# Peripherals.net
KiCad netlist of a schematic drawn in Altium Designer
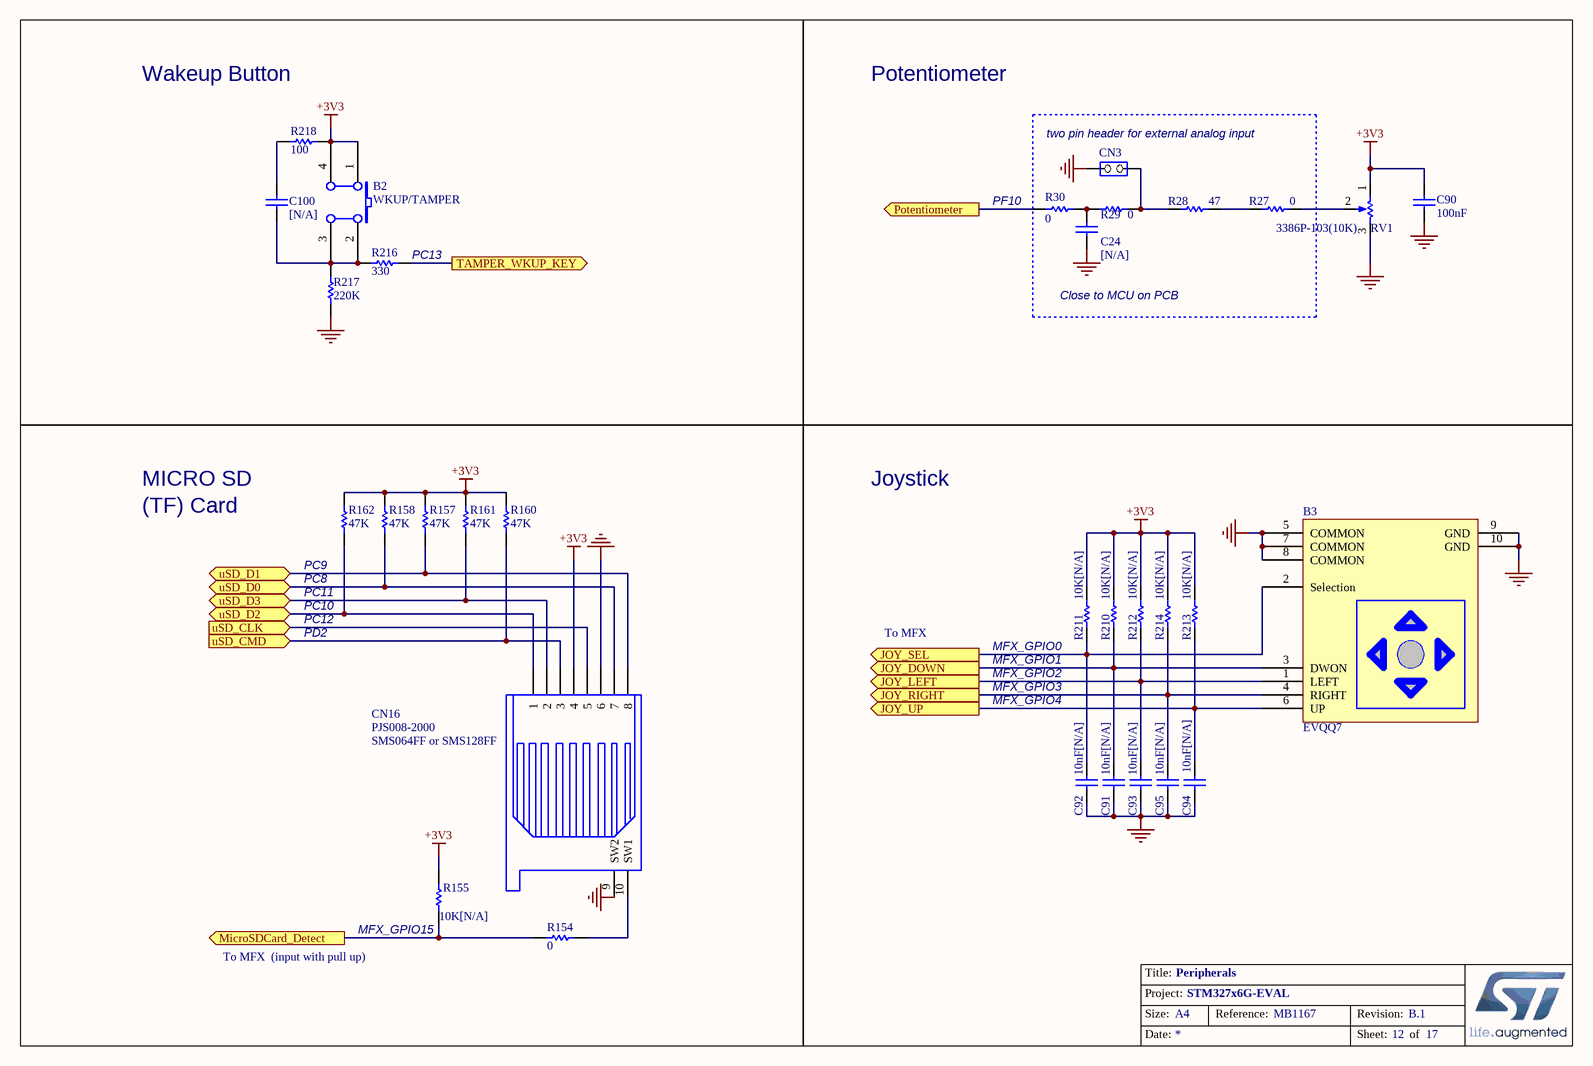
[diagram p0: Peripherals.SchDoc]

(export (version "E")
  (design (tool "Eeschema 10.0.6"))
  (components
    (comp (ref "B2")
      (value "WKUP/TAMPER")
      (footprint "PB10")
      (description "SE PUSHBUTTON")
      (libsource (lib "Documents") (part "SW PUSHBUTTON"))
    )
    (comp (ref "B3") (value "EVQQ7") (footprint "SW-JOY") (libsource (lib "mb1045") (part "EVQQ7")))
    (comp (ref "C24")
      (value "[N/A]")
      (footprint "0603C")
      (description "Capacitor")
      (fields (field (name "PUBLISHER") "Altium Limited"))
      (libsource (lib "Miscellaneous Devices") (part "cap"))
    )
    (comp (ref "C90")
      (value "100nF")
      (footprint "0603C")
      (description "Capacitor")
      (fields (field (name "PUBLISHER") "Altium Limited"))
      (libsource (lib "Miscellaneous Devices") (part "CAP"))
    )
    (comp (ref "C91")
      (value "10nF[N/A]")
      (footprint "0603C")
      (description "Capacitor")
      (fields (field (name "PUBLISHER") "Altium Limited"))
      (libsource (lib "Miscellaneous Devices") (part "CAP"))
    )
    (comp (ref "C92")
      (value "10nF[N/A]")
      (footprint "0603C")
      (description "Capacitor")
      (fields (field (name "PUBLISHER") "Altium Limited"))
      (libsource (lib "Miscellaneous Devices") (part "CAP"))
    )
    (comp (ref "C93")
      (value "10nF[N/A]")
      (footprint "0603C")
      (description "Capacitor")
      (fields (field (name "PUBLISHER") "Altium Limited"))
      (libsource (lib "Miscellaneous Devices") (part "CAP"))
    )
    (comp (ref "C94")
      (value "10nF[N/A]")
      (footprint "0603C")
      (description "Capacitor")
      (fields (field (name "PUBLISHER") "Altium Limited"))
      (libsource (lib "Miscellaneous Devices") (part "CAP"))
    )
    (comp (ref "C95")
      (value "10nF[N/A]")
      (footprint "0603C")
      (description "Capacitor")
      (fields (field (name "PUBLISHER") "Altium Limited"))
      (libsource (lib "Miscellaneous Devices") (part "CAP"))
    )
    (comp (ref "C100")
      (value "[N/A]")
      (footprint "0603C")
      (description "Capacitor")
      (fields (field (name "PUBLISHER") "Altium Limited"))
      (libsource (lib "Miscellaneous Devices") (part "CAP"))
    )
    (comp (ref "CN3") (value "~") (footprint "SIP2") (libsource (lib "*") (part "JP2")))
    (comp (ref "CN16")
      (value "PJS008-2000")
      (footprint "MSD_PJS008_")
      (libsource (lib "MB525") (part "SMS016AFA5E"))
    )
    (comp (ref "R27")
      (value "0")
      (footprint "0603R")
      (description "Resistor")
      (fields (field (name "PUBLISHER") "Altium Limited"))
      (libsource (lib "Miscellaneous Devices") (part "Res1"))
    )
    (comp (ref "R28")
      (value "47")
      (footprint "0603R")
      (description "Resistor")
      (fields (field (name "PUBLISHER") "Altium Limited"))
      (libsource (lib "Miscellaneous Devices") (part "Res1"))
    )
    (comp (ref "R29")
      (value "0")
      (footprint "0603R")
      (description "Resistor")
      (fields (field (name "PUBLISHER") "Altium Limited"))
      (libsource (lib "Miscellaneous Devices") (part "Res1"))
    )
    (comp (ref "R30")
      (value "0")
      (footprint "0603R")
      (description "Resistor")
      (fields (field (name "PUBLISHER") "Altium Limited"))
      (libsource (lib "Miscellaneous Devices") (part "Res1"))
    )
    (comp (ref "R154")
      (value "0")
      (footprint "0603R")
      (description "Resistor")
      (fields (field (name "PUBLISHER") "Altium Limited"))
      (libsource (lib "Miscellaneous Devices") (part "Res1"))
    )
    (comp (ref "R155")
      (value "10K[N/A]")
      (footprint "0603R")
      (description "Resistor")
      (fields (field (name "PUBLISHER") "Altium Limited"))
      (libsource (lib "Miscellaneous Devices") (part "Res1"))
    )
    (comp (ref "R157")
      (value "47K")
      (footprint "0603R")
      (description "Resistor")
      (fields (field (name "PUBLISHER") "Altium Limited"))
      (libsource (lib "Miscellaneous Devices") (part "res1"))
    )
    (comp (ref "R158")
      (value "47K")
      (footprint "0603R")
      (description "Resistor")
      (fields (field (name "PUBLISHER") "Altium Limited"))
      (libsource (lib "Miscellaneous Devices") (part "res1"))
    )
    (comp (ref "R160")
      (value "47K")
      (footprint "0603R")
      (description "Resistor")
      (fields (field (name "PUBLISHER") "Altium Limited"))
      (libsource (lib "Miscellaneous Devices") (part "res1"))
    )
    (comp (ref "R161")
      (value "47K")
      (footprint "0603R")
      (description "Resistor")
      (fields (field (name "PUBLISHER") "Altium Limited"))
      (libsource (lib "Miscellaneous Devices") (part "res1"))
    )
    (comp (ref "R162")
      (value "47K")
      (footprint "0603R")
      (description "Resistor")
      (fields (field (name "PUBLISHER") "Altium Limited"))
      (libsource (lib "Miscellaneous Devices") (part "res1"))
    )
    (comp (ref "R210")
      (value "10K[N/A]")
      (footprint "0603R")
      (description "Resistor")
      (fields (field (name "PUBLISHER") "Altium Limited"))
      (libsource (lib "Miscellaneous Devices") (part "res1"))
    )
    (comp (ref "R211")
      (value "10K[N/A]")
      (footprint "0603R")
      (description "Resistor")
      (fields (field (name "PUBLISHER") "Altium Limited"))
      (libsource (lib "Miscellaneous Devices") (part "res1"))
    )
    (comp (ref "R212")
      (value "10K[N/A]")
      (footprint "0603R")
      (description "Resistor")
      (fields (field (name "PUBLISHER") "Altium Limited"))
      (libsource (lib "Miscellaneous Devices") (part "res1"))
    )
    (comp (ref "R213")
      (value "10K[N/A]")
      (footprint "0603R")
      (description "Resistor")
      (fields (field (name "PUBLISHER") "Altium Limited"))
      (libsource (lib "Miscellaneous Devices") (part "res1"))
    )
    (comp (ref "R214")
      (value "10K[N/A]")
      (footprint "0603R")
      (description "Resistor")
      (fields (field (name "PUBLISHER") "Altium Limited"))
      (libsource (lib "Miscellaneous Devices") (part "res1"))
    )
    (comp (ref "R216")
      (value "330")
      (footprint "0603R")
      (description "Resistor")
      (fields (field (name "PUBLISHER") "Altium Limited"))
      (libsource (lib "Miscellaneous Devices") (part "Res1"))
    )
    (comp (ref "R217")
      (value "220K")
      (footprint "0603R")
      (description "Resistor")
      (fields (field (name "PUBLISHER") "Altium Limited"))
      (libsource (lib "Miscellaneous Devices") (part "res1"))
    )
    (comp (ref "R218")
      (value "100")
      (footprint "0603R")
      (description "Resistor")
      (fields (field (name "PUBLISHER") "Altium Limited"))
      (libsource (lib "Miscellaneous Devices") (part "Res1"))
    )
    (comp (ref "RV1")
      (value "3386P-103(10K)")
      (footprint "3386P")
      (libsource (lib "STR910_SCHLIB") (part "RV"))
    )
  )
  (nets
    (net (code "1") (name "+3V3") (class "Default")
      (node (ref "B2") (pin "1") (pinfunction "A0_1") (pintype "passive"))
      (node (ref "B2") (pin "4") (pinfunction "A1_4") (pintype "passive"))
      (node (ref "C90") (pin "1") (pinfunction "1_1") (pintype "passive"))
      (node (ref "CN16") (pin "4") (pinfunction "4_4") (pintype "passive"))
      (node (ref "R155") (pin "2") (pinfunction "2_2") (pintype "passive"))
      (node (ref "R157") (pin "1") (pinfunction "1_1") (pintype "passive"))
      (node (ref "R158") (pin "1") (pinfunction "1_1") (pintype "passive"))
      (node (ref "R160") (pin "1") (pinfunction "1_1") (pintype "passive"))
      (node (ref "R161") (pin "1") (pinfunction "1_1") (pintype "passive"))
      (node (ref "R162") (pin "1") (pinfunction "1_1") (pintype "passive"))
      (node (ref "R210") (pin "1") (pinfunction "1_1") (pintype "passive"))
      (node (ref "R211") (pin "1") (pinfunction "1_1") (pintype "passive"))
      (node (ref "R212") (pin "1") (pinfunction "1_1") (pintype "passive"))
      (node (ref "R213") (pin "1") (pinfunction "1_1") (pintype "passive"))
      (node (ref "R214") (pin "1") (pinfunction "1_1") (pintype "passive"))
      (node (ref "R218") (pin "1") (pinfunction "1_1") (pintype "passive"))
      (node (ref "RV1") (pin "1") (pinfunction "BOT_1") (pintype "passive"))
    )
    (net (code "2") (name "/JOY_DOWN") (class "Default")
      (node (ref "B3") (pin "3") (pinfunction "DWON_3") (pintype "passive"))
      (node (ref "C91") (pin "2") (pinfunction "2_2") (pintype "passive"))
      (node (ref "R210") (pin "2") (pinfunction "2_2") (pintype "passive"))
    )
    (net (code "3") (name "/JOY_LEFT") (class "Default")
      (node (ref "B3") (pin "1") (pinfunction "LEFT_1") (pintype "passive"))
      (node (ref "C93") (pin "2") (pinfunction "2_2") (pintype "passive"))
      (node (ref "R212") (pin "2") (pinfunction "2_2") (pintype "passive"))
    )
    (net (code "4") (name "/JOY_RIGHT") (class "Default")
      (node (ref "B3") (pin "4") (pinfunction "RIGHT_4") (pintype "passive"))
      (node (ref "C95") (pin "2") (pinfunction "2_2") (pintype "passive"))
      (node (ref "R214") (pin "2") (pinfunction "2_2") (pintype "passive"))
    )
    (net (code "5") (name "/JOY_SEL") (class "Default")
      (node (ref "B3") (pin "2") (pinfunction "Selection_2") (pintype "passive"))
      (node (ref "C92") (pin "2") (pinfunction "2_2") (pintype "passive"))
      (node (ref "R211") (pin "2") (pinfunction "2_2") (pintype "passive"))
    )
    (net (code "6") (name "/JOY_UP") (class "Default")
      (node (ref "B3") (pin "6") (pinfunction "UP_6") (pintype "passive"))
      (node (ref "C94") (pin "2") (pinfunction "2_2") (pintype "passive"))
      (node (ref "R213") (pin "2") (pinfunction "2_2") (pintype "passive"))
    )
    (net (code "7") (name "/MicroSDCard_Detect") (class "Default")
      (node (ref "R154") (pin "1") (pinfunction "1_1") (pintype "passive"))
      (node (ref "R155") (pin "1") (pinfunction "1_1") (pintype "passive"))
    )
    (net (code "8") (name "/Potentiometer") (class "Default")
      (node (ref "R30") (pin "2") (pinfunction "2_2") (pintype "passive"))
    )
    (net (code "9") (name "/TAMPER_WKUP_KEY") (class "Default")
      (node (ref "R216") (pin "2") (pinfunction "2_2") (pintype "passive"))
    )
    (net (code "10") (name "/uSD_CLK") (class "Default")
      (node (ref "CN16") (pin "5") (pinfunction "5_5") (pintype "passive"))
    )
    (net (code "11") (name "/uSD_CMD") (class "Default")
      (node (ref "CN16") (pin "3") (pinfunction "3_3") (pintype "passive"))
      (node (ref "R160") (pin "2") (pinfunction "2_2") (pintype "passive"))
    )
    (net (code "12") (name "/uSD_D0") (class "Default")
      (node (ref "CN16") (pin "7") (pinfunction "7_7") (pintype "passive"))
      (node (ref "R158") (pin "2") (pinfunction "2_2") (pintype "passive"))
    )
    (net (code "13") (name "/uSD_D1") (class "Default")
      (node (ref "CN16") (pin "8") (pinfunction "8_8") (pintype "passive"))
      (node (ref "R157") (pin "2") (pinfunction "2_2") (pintype "passive"))
    )
    (net (code "14") (name "/uSD_D2") (class "Default")
      (node (ref "CN16") (pin "1") (pinfunction "1_1") (pintype "passive"))
      (node (ref "R162") (pin "2") (pinfunction "2_2") (pintype "passive"))
    )
    (net (code "15") (name "/uSD_D3") (class "Default")
      (node (ref "CN16") (pin "2") (pinfunction "2_2") (pintype "passive"))
      (node (ref "R161") (pin "2") (pinfunction "2_2") (pintype "passive"))
    )
    (net (code "16") (name "GND") (class "Default")
      (node (ref "B3") (pin "10") (pinfunction "GND_10") (pintype "passive"))
      (node (ref "B3") (pin "5") (pinfunction "COMMON_5") (pintype "passive"))
      (node (ref "B3") (pin "7") (pinfunction "COMMON_7") (pintype "passive"))
      (node (ref "B3") (pin "8") (pinfunction "COMMON_8") (pintype "passive"))
      (node (ref "B3") (pin "9") (pinfunction "GND_9") (pintype "passive"))
      (node (ref "C24") (pin "1") (pinfunction "1_1") (pintype "passive"))
      (node (ref "C90") (pin "2") (pinfunction "2_2") (pintype "passive"))
      (node (ref "C91") (pin "1") (pinfunction "1_1") (pintype "passive"))
      (node (ref "C92") (pin "1") (pinfunction "1_1") (pintype "passive"))
      (node (ref "C93") (pin "1") (pinfunction "1_1") (pintype "passive"))
      (node (ref "C94") (pin "1") (pinfunction "1_1") (pintype "passive"))
      (node (ref "C95") (pin "1") (pinfunction "1_1") (pintype "passive"))
      (node (ref "CN16") (pin "6") (pinfunction "6_6") (pintype "passive"))
      (node (ref "CN16") (pin "9") (pinfunction "SW2_9") (pintype "passive"))
      (node (ref "CN3") (pin "2") (pinfunction "NO_2") (pintype "passive"))
      (node (ref "R217") (pin "2") (pinfunction "2_2") (pintype "passive"))
      (node (ref "RV1") (pin "3") (pinfunction "TOP_3") (pintype "passive"))
    )
    (net (code "17") (name "Net-(B2-B0)") (class "Default")
      (node (ref "B2") (pin "2") (pinfunction "B0_2") (pintype "passive"))
      (node (ref "B2") (pin "3") (pinfunction "B1_3") (pintype "passive"))
      (node (ref "C100") (pin "2") (pinfunction "2_2") (pintype "passive"))
      (node (ref "R216") (pin "1") (pinfunction "1_1") (pintype "passive"))
      (node (ref "R217") (pin "1") (pinfunction "1_1") (pintype "passive"))
    )
    (net (code "18") (name "Net-(C24-Pad2)") (class "Default")
      (node (ref "C24") (pin "2") (pinfunction "2_2") (pintype "passive"))
      (node (ref "R29") (pin "1") (pinfunction "1_1") (pintype "passive"))
      (node (ref "R30") (pin "1") (pinfunction "1_1") (pintype "passive"))
    )
    (net (code "19") (name "Net-(C100-Pad1)") (class "Default")
      (node (ref "C100") (pin "1") (pinfunction "1_1") (pintype "passive"))
      (node (ref "R218") (pin "2") (pinfunction "2_2") (pintype "passive"))
    )
    (net (code "20") (name "Net-(CN3-COMMON)") (class "Default")
      (node (ref "CN3") (pin "1") (pinfunction "COMMON_1") (pintype "passive"))
      (node (ref "R28") (pin "1") (pinfunction "1_1") (pintype "passive"))
      (node (ref "R29") (pin "2") (pinfunction "2_2") (pintype "passive"))
    )
    (net (code "21") (name "Net-(CN16-SW1)") (class "Default")
      (node (ref "CN16") (pin "10") (pinfunction "SW1_10") (pintype "passive"))
      (node (ref "R154") (pin "2") (pinfunction "2_2") (pintype "passive"))
    )
    (net (code "22") (name "Net-(R27-Pad1)") (class "Default")
      (node (ref "R27") (pin "1") (pinfunction "1_1") (pintype "passive"))
      (node (ref "R28") (pin "2") (pinfunction "2_2") (pintype "passive"))
    )
    (net (code "23") (name "Net-(RV1-TAP)") (class "Default")
      (node (ref "R27") (pin "2") (pinfunction "2_2") (pintype "passive"))
      (node (ref "RV1") (pin "2") (pinfunction "TAP_2") (pintype "passive"))
    )
  )
)
